# bleumaus-nrf51822-mk-1_0_1.net
KiCad netlist of a schematic drawn in EAGLE
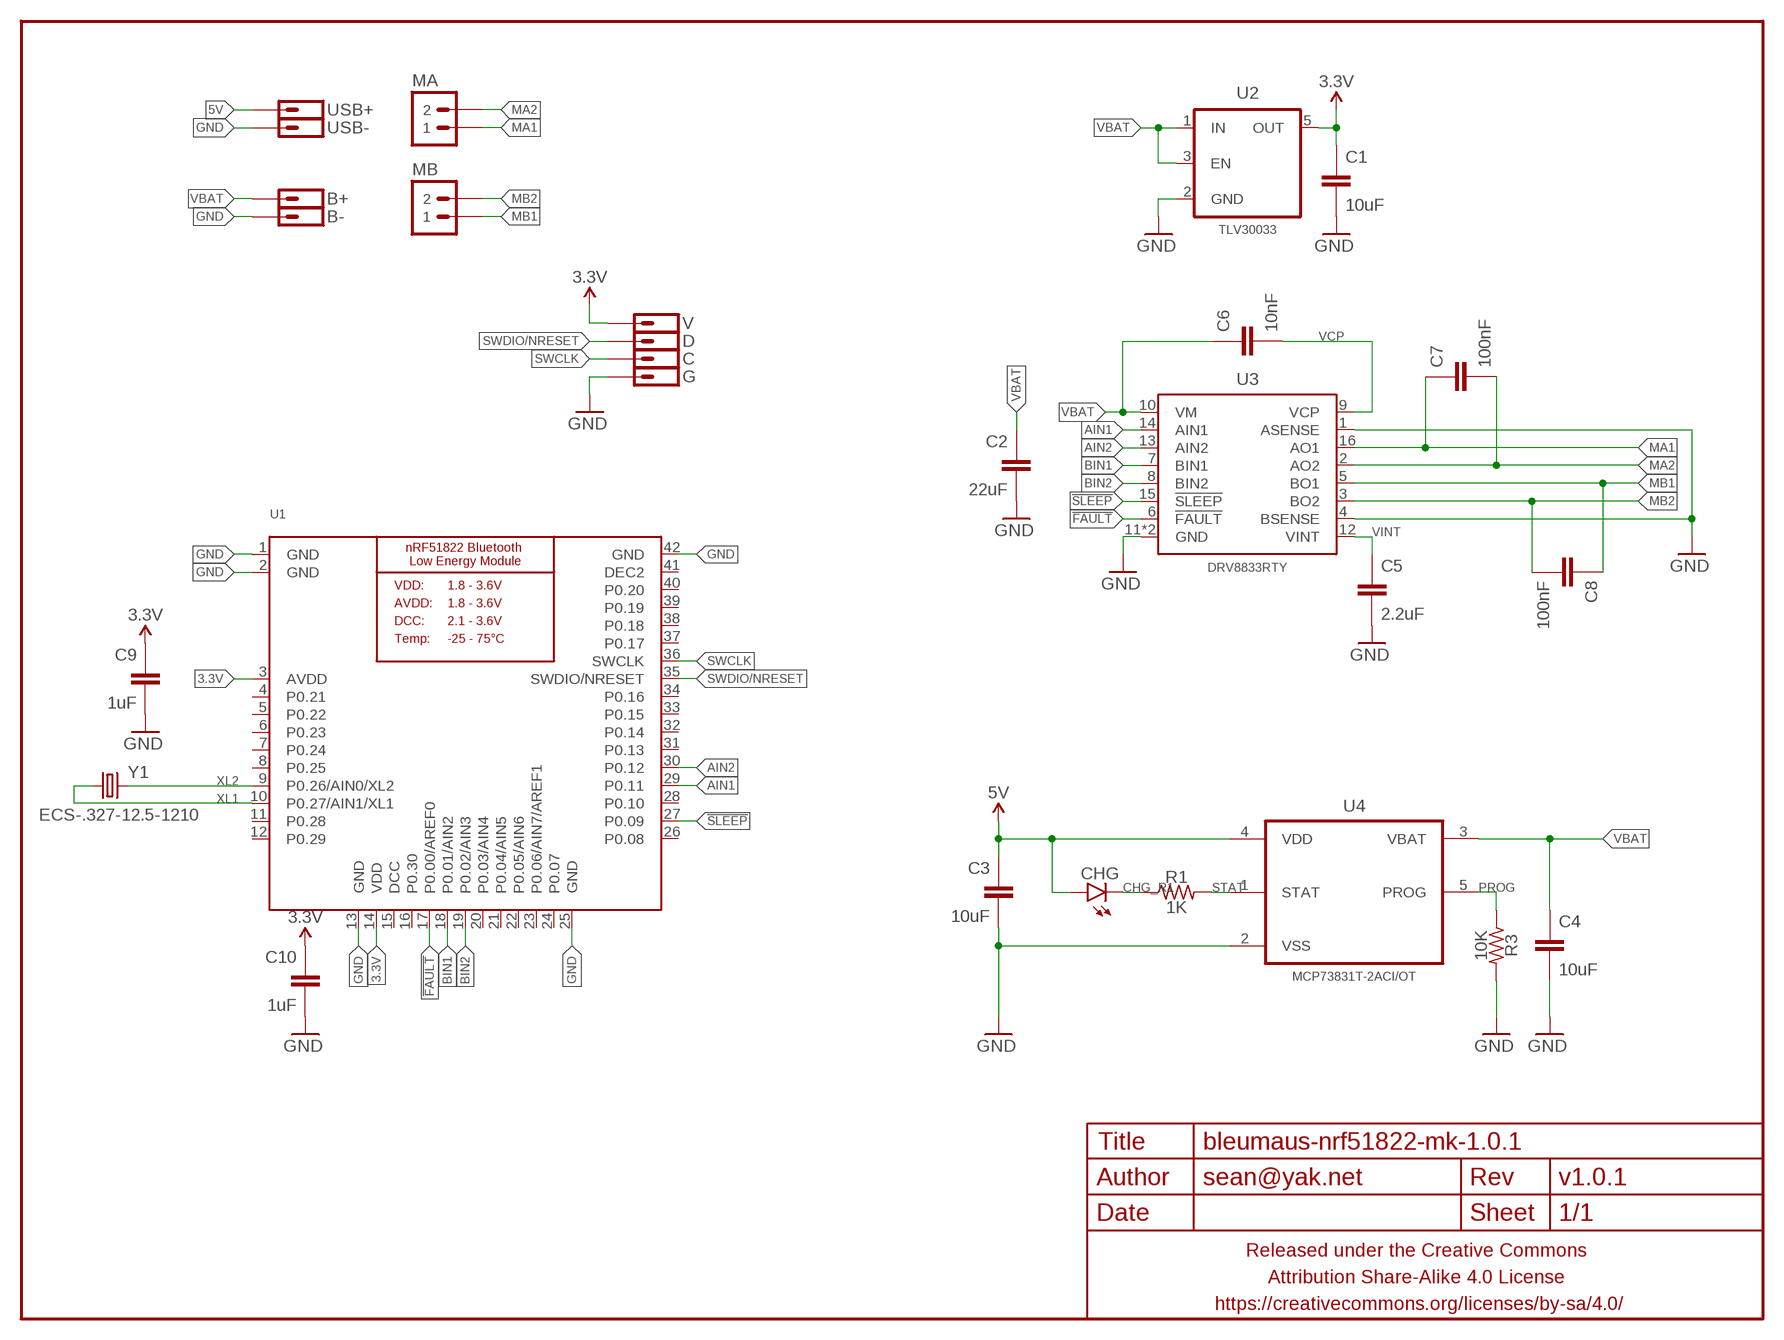
[diagram p0: schematic, sheet 1]

(export (version "E")
  (design (tool "Eeschema 10.0.6"))
  (components
    (comp (ref "B+")
      (value "M01SMD-1DIA")
      (footprint "eagle-import:1X01-SMD-1MM-DIA")
      (libsource (lib "eagle-import") (part "M01SMD-1DIA"))
    )
    (comp (ref "B-")
      (value "M01SMD-1DIA")
      (footprint "eagle-import:1X01-SMD-1MM-DIA")
      (libsource (lib "eagle-import") (part "M01SMD-1DIA"))
    )
    (comp (ref "C")
      (value "M01SMD-1DIA")
      (footprint "eagle-import:1X01-SMD-1MM-DIA")
      (libsource (lib "eagle-import") (part "M01SMD-1DIA"))
    )
    (comp (ref "C1")
      (value "10uF")
      (footprint "eagle-import:C0402")
      (libsource (lib "eagle-import") (part "CAPACITOR-CERAMICC0402"))
    )
    (comp (ref "C2")
      (value "22uF")
      (footprint "eagle-import:C1206")
      (libsource (lib "eagle-import") (part "CAPACITOR-CERAMICC1206"))
    )
    (comp (ref "C3")
      (value "10uF")
      (footprint "eagle-import:C0402")
      (libsource (lib "eagle-import") (part "CAPACITOR-CERAMICC0402"))
    )
    (comp (ref "C4")
      (value "10uF")
      (footprint "eagle-import:C0402")
      (libsource (lib "eagle-import") (part "CAPACITOR-CERAMICC0402"))
    )
    (comp (ref "C5")
      (value "2.2uF")
      (footprint "eagle-import:C0402")
      (libsource (lib "eagle-import") (part "CAPACITOR-CERAMICC0402"))
    )
    (comp (ref "C6")
      (value "10nF")
      (footprint "eagle-import:C0402")
      (libsource (lib "eagle-import") (part "CAPACITOR-CERAMICC0402"))
    )
    (comp (ref "C7")
      (value "100nF")
      (footprint "eagle-import:C0402")
      (libsource (lib "eagle-import") (part "CAPACITOR-CERAMICC0402"))
    )
    (comp (ref "C8")
      (value "100nF")
      (footprint "eagle-import:C0402")
      (libsource (lib "eagle-import") (part "CAPACITOR-CERAMICC0402"))
    )
    (comp (ref "C9")
      (value "1uF")
      (footprint "eagle-import:C0402")
      (libsource (lib "eagle-import") (part "CAPACITOR-CERAMICC0402"))
    )
    (comp (ref "C10")
      (value "1uF")
      (footprint "eagle-import:C0402")
      (libsource (lib "eagle-import") (part "CAPACITOR-CERAMICC0402"))
    )
    (comp (ref "CHG")
      (value "LED0603-TIGHT")
      (footprint "eagle-import:LED-0603-TIGHT")
      (libsource (lib "eagle-import") (part "LED0603-TIGHT"))
    )
    (comp (ref "D")
      (value "M01SMD-1DIA")
      (footprint "eagle-import:1X01-SMD-1MM-DIA")
      (libsource (lib "eagle-import") (part "M01SMD-1DIA"))
    )
    (comp (ref "FRAME1")
      (value "FRAME-LETTERNO_PACKAGE")
      (footprint "eagle-import:DUMMY")
      (fields
        (field (name "DESIGNER") "sean@yak.net")
        (field (name "VERSION") "v1.0.1")
        (field (name "DESIGNER_1") "sean@yak.net")
        (field (name "VERSION_1") "v1.0.1")
      )
      (libsource (lib "eagle-import") (part "FRAME-LETTERNO_PACKAGE"))
    )
    (comp (ref "G")
      (value "M01SMD-1DIA")
      (footprint "eagle-import:1X01-SMD-1MM-DIA")
      (libsource (lib "eagle-import") (part "M01SMD-1DIA"))
    )
    (comp (ref "MA")
      (value "M02PTH-2MM")
      (footprint "eagle-import:1X02-2MM-PTH")
      (libsource (lib "eagle-import") (part "M02PTH-2MM"))
    )
    (comp (ref "MB")
      (value "M02PTH-2MM")
      (footprint "eagle-import:1X02-2MM-PTH")
      (libsource (lib "eagle-import") (part "M02PTH-2MM"))
    )
    (comp (ref "R1")
      (value "1K")
      (footprint "eagle-import:R0402")
      (libsource (lib "eagle-import") (part "RESISTORR0402"))
    )
    (comp (ref "R3")
      (value "10K")
      (footprint "eagle-import:R0402")
      (libsource (lib "eagle-import") (part "RESISTORR0402"))
    )
    (comp (ref "U1")
      (value "NRF51822_MODULE_MDBT40")
      (footprint "eagle-import:BLE_MODULE_RAYTAC_MDBT40")
      (libsource (lib "eagle-import") (part "NRF51822_MODULE_MDBT40"))
    )
    (comp (ref "U2")
      (value "TLV30033")
      (footprint "eagle-import:SC70-TIGHTER")
      (libsource (lib "eagle-import") (part "V_REG_ENTLV700XXDCK-TIGHTER"))
    )
    (comp (ref "U3")
      (value "DRV8833RTY")
      (footprint "eagle-import:PWQFN-16")
      (libsource (lib "eagle-import") (part "DRV8833RTY"))
    )
    (comp (ref "U4")
      (value "MCP73831T-2ACI/OT")
      (footprint "eagle-import:SOT95P280X145-5N")
      (libsource (lib "eagle-import") (part "MCP73831T-2ACI/OT"))
    )
    (comp (ref "USB+")
      (value "M01SMD-1DIA")
      (footprint "eagle-import:1X01-SMD-1MM-DIA")
      (libsource (lib "eagle-import") (part "M01SMD-1DIA"))
    )
    (comp (ref "USB-")
      (value "M01SMD-1DIA")
      (footprint "eagle-import:1X01-SMD-1MM-DIA")
      (libsource (lib "eagle-import") (part "M01SMD-1DIA"))
    )
    (comp (ref "V")
      (value "M01SMD-1DIA")
      (footprint "eagle-import:1X01-SMD-1MM-DIA")
      (libsource (lib "eagle-import") (part "M01SMD-1DIA"))
    )
    (comp (ref "Y1")
      (value "ECS-.327-12.5-1210")
      (footprint "eagle-import:CRYSTAL-1X1.2MM")
      (libsource (lib "eagle-import") (part "CRYSTAL1X1.2MM"))
    )
  )
  (nets
    (net (code "1") (name "/CHG_R1") (class "Default")
      (node (ref "CHG") (pin "C") (pinfunction "C_C") (pintype "passive"))
      (node (ref "R1") (pin "1") (pinfunction "1_1") (pintype "passive"))
    )
    (net (code "2") (name "/DCC") (class "Default")
      (node (ref "U1") (pin "15") (pinfunction "DCC_15") (pintype "power_in"))
    )
    (net (code "3") (name "/DEC2") (class "Default")
      (node (ref "U1") (pin "41") (pinfunction "DEC2_41") (pintype "power_in"))
    )
    (net (code "4") (name "/PROG") (class "Default")
      (node (ref "R3") (pin "1") (pinfunction "1_1") (pintype "passive"))
      (node (ref "U4") (pin "5") (pinfunction "PROG_5") (pintype "input"))
    )
    (net (code "5") (name "/STAT") (class "Default")
      (node (ref "R1") (pin "2") (pinfunction "2_2") (pintype "passive"))
      (node (ref "U4") (pin "1") (pinfunction "STAT_1") (pintype "output"))
    )
    (net (code "6") (name "/VCP") (class "Default")
      (node (ref "C6") (pin "2") (pinfunction "2_2") (pintype "passive"))
      (node (ref "U3") (pin "9") (pinfunction "VCP_9") (pintype "bidirectional"))
    )
    (net (code "7") (name "/VINT") (class "Default")
      (node (ref "C5") (pin "1") (pinfunction "1_1") (pintype "passive"))
      (node (ref "U3") (pin "12") (pinfunction "VINT_12") (pintype "bidirectional"))
    )
    (net (code "8") (name "/XL1") (class "Default")
      (node (ref "U1") (pin "10") (pinfunction "P0.27/AIN1/XL1_10") (pintype "bidirectional"))
      (node (ref "Y1") (pin "1") (pinfunction "1_1") (pintype "passive"))
    )
    (net (code "9") (name "/XL2") (class "Default")
      (node (ref "U1") (pin "9") (pinfunction "P0.26/AIN0/XL2_9") (pintype "bidirectional"))
      (node (ref "Y1") (pin "2") (pinfunction "2_2") (pintype "passive"))
    )
    (net (code "10") (name "/~{FAULT}") (class "Default")
      (node (ref "U1") (pin "17") (pinfunction "P0.00/AREF0_17") (pintype "bidirectional"))
      (node (ref "U3") (pin "6") (pinfunction "~{FAULT}_6") (pintype "output"))
    )
    (net (code "11") (name "/~{SLEEP}") (class "Default")
      (node (ref "U1") (pin "27") (pinfunction "P0.09_27") (pintype "bidirectional"))
      (node (ref "U3") (pin "15") (pinfunction "~{SLEEP}_15") (pintype "input"))
    )
    (net (code "12") (name "3.3V") (class "Default")
      (node (ref "C1") (pin "1") (pinfunction "1_1") (pintype "passive"))
      (node (ref "C10") (pin "1") (pinfunction "1_1") (pintype "passive"))
      (node (ref "C9") (pin "1") (pinfunction "1_1") (pintype "passive"))
      (node (ref "U1") (pin "14") (pinfunction "VDD_14") (pintype "power_in"))
      (node (ref "U1") (pin "3") (pinfunction "AVDD_3") (pintype "power_in"))
      (node (ref "U2") (pin "5") (pinfunction "OUT_5") (pintype "passive"))
      (node (ref "V") (pin "P$1") (pinfunction "1_P$1") (pintype "passive"))
    )
    (net (code "13") (name "5V") (class "Default")
      (node (ref "C3") (pin "1") (pinfunction "1_1") (pintype "passive"))
      (node (ref "CHG") (pin "A") (pinfunction "A_A") (pintype "passive"))
      (node (ref "U4") (pin "4") (pinfunction "VDD_4") (pintype "power_in"))
      (node (ref "USB+") (pin "P$1") (pinfunction "1_P$1") (pintype "passive"))
    )
    (net (code "14") (name "AIN1") (class "Default")
      (node (ref "U1") (pin "29") (pinfunction "P0.11_29") (pintype "bidirectional"))
      (node (ref "U3") (pin "14") (pinfunction "AIN1_14") (pintype "input"))
    )
    (net (code "15") (name "AIN2") (class "Default")
      (node (ref "U1") (pin "30") (pinfunction "P0.12_30") (pintype "bidirectional"))
      (node (ref "U3") (pin "13") (pinfunction "AIN2_13") (pintype "input"))
    )
    (net (code "16") (name "BIN1") (class "Default")
      (node (ref "U1") (pin "18") (pinfunction "P0.01/AIN2_18") (pintype "bidirectional"))
      (node (ref "U3") (pin "7") (pinfunction "BIN1_7") (pintype "input"))
    )
    (net (code "17") (name "BIN2") (class "Default")
      (node (ref "U1") (pin "19") (pinfunction "P0.02/AIN3_19") (pintype "bidirectional"))
      (node (ref "U3") (pin "8") (pinfunction "BIN2_8") (pintype "input"))
    )
    (net (code "18") (name "GND") (class "Default")
      (node (ref "B-") (pin "P$1") (pinfunction "1_P$1") (pintype "passive"))
      (node (ref "C1") (pin "2") (pinfunction "2_2") (pintype "passive"))
      (node (ref "C10") (pin "2") (pinfunction "2_2") (pintype "passive"))
      (node (ref "C2") (pin "2") (pinfunction "2_2") (pintype "passive"))
      (node (ref "C3") (pin "2") (pinfunction "2_2") (pintype "passive"))
      (node (ref "C4") (pin "2") (pinfunction "2_2") (pintype "passive"))
      (node (ref "C5") (pin "2") (pinfunction "2_2") (pintype "passive"))
      (node (ref "C9") (pin "2") (pinfunction "2_2") (pintype "passive"))
      (node (ref "G") (pin "P$1") (pinfunction "1_P$1") (pintype "passive"))
      (node (ref "R3") (pin "2") (pinfunction "2_2") (pintype "passive"))
      (node (ref "U1") (pin "1") (pinfunction "GND_1") (pintype "power_in"))
      (node (ref "U1") (pin "13") (pinfunction "GND_13") (pintype "power_in"))
      (node (ref "U1") (pin "2") (pinfunction "GND_2") (pintype "power_in"))
      (node (ref "U1") (pin "25") (pinfunction "GND_25") (pintype "power_in"))
      (node (ref "U1") (pin "42") (pinfunction "GND_42") (pintype "power_in"))
      (node (ref "U2") (pin "2") (pinfunction "GND_2") (pintype "input"))
      (node (ref "U3") (pin "1") (pinfunction "ASENSE_1") (pintype "bidirectional"))
      (node (ref "U3") (pin "11") (pinfunction "GND_11") (pintype "bidirectional"))
      (node (ref "U3") (pin "17") (pinfunction "GND_17") (pintype "bidirectional"))
      (node (ref "U3") (pin "4") (pinfunction "BSENSE_4") (pintype "bidirectional"))
      (node (ref "U4") (pin "2") (pinfunction "VSS_2") (pintype "power_in"))
      (node (ref "USB-") (pin "P$1") (pinfunction "1_P$1") (pintype "passive"))
    )
    (net (code "19") (name "MA1") (class "Default")
      (node (ref "C7") (pin "1") (pinfunction "1_1") (pintype "passive"))
      (node (ref "MA") (pin "P$1") (pinfunction "1_P$1") (pintype "passive"))
      (node (ref "U3") (pin "16") (pinfunction "AO1_16") (pintype "bidirectional"))
    )
    (net (code "20") (name "MA2") (class "Default")
      (node (ref "C7") (pin "2") (pinfunction "2_2") (pintype "passive"))
      (node (ref "MA") (pin "P$2") (pinfunction "2_P$2") (pintype "passive"))
      (node (ref "U3") (pin "2") (pinfunction "AO2_2") (pintype "bidirectional"))
    )
    (net (code "21") (name "MB1") (class "Default")
      (node (ref "C8") (pin "1") (pinfunction "1_1") (pintype "passive"))
      (node (ref "MB") (pin "P$1") (pinfunction "1_P$1") (pintype "passive"))
      (node (ref "U3") (pin "5") (pinfunction "BO1_5") (pintype "bidirectional"))
    )
    (net (code "22") (name "MB2") (class "Default")
      (node (ref "C8") (pin "2") (pinfunction "2_2") (pintype "passive"))
      (node (ref "MB") (pin "P$2") (pinfunction "2_P$2") (pintype "passive"))
      (node (ref "U3") (pin "3") (pinfunction "BO2_3") (pintype "bidirectional"))
    )
    (net (code "23") (name "SWCLK") (class "Default")
      (node (ref "C") (pin "P$1") (pinfunction "1_P$1") (pintype "passive"))
      (node (ref "U1") (pin "36") (pinfunction "SWCLK_36") (pintype "bidirectional"))
    )
    (net (code "24") (name "SWDIO{slash}NRESET") (class "Default")
      (node (ref "D") (pin "P$1") (pinfunction "1_P$1") (pintype "passive"))
      (node (ref "U1") (pin "35") (pinfunction "SWDIO/NRESET_35") (pintype "bidirectional"))
    )
    (net (code "25") (name "VBAT") (class "Default")
      (node (ref "B+") (pin "P$1") (pinfunction "1_P$1") (pintype "passive"))
      (node (ref "C2") (pin "1") (pinfunction "1_1") (pintype "passive"))
      (node (ref "C4") (pin "1") (pinfunction "1_1") (pintype "passive"))
      (node (ref "C6") (pin "1") (pinfunction "1_1") (pintype "passive"))
      (node (ref "U2") (pin "1") (pinfunction "IN_1") (pintype "input"))
      (node (ref "U2") (pin "3") (pinfunction "EN_3") (pintype "input"))
      (node (ref "U3") (pin "10") (pinfunction "VM_10") (pintype "bidirectional"))
      (node (ref "U4") (pin "3") (pinfunction "VBAT_3") (pintype "output"))
    )
    (net (code "26") (name "unconnected-(U1-P0.03{slash}AIN4-Pad20)") (class "Default")
      (node (ref "U1") (pin "20") (pinfunction "P0.03/AIN4_20") (pintype "bidirectional"))
    )
    (net (code "27") (name "unconnected-(U1-P0.04{slash}AIN5-Pad21)") (class "Default")
      (node (ref "U1") (pin "21") (pinfunction "P0.04/AIN5_21") (pintype "bidirectional"))
    )
    (net (code "28") (name "unconnected-(U1-P0.05{slash}AIN6-Pad22)") (class "Default")
      (node (ref "U1") (pin "22") (pinfunction "P0.05/AIN6_22") (pintype "bidirectional"))
    )
    (net (code "29") (name "unconnected-(U1-P0.06{slash}AIN7{slash}AREF1-Pad23)") (class "Default")
      (node (ref "U1") (pin "23") (pinfunction "P0.06/AIN7/AREF1_23") (pintype "bidirectional"))
    )
    (net (code "30") (name "unconnected-(U1-P0.07-Pad24)") (class "Default")
      (node (ref "U1") (pin "24") (pinfunction "P0.07_24") (pintype "bidirectional"))
    )
    (net (code "31") (name "unconnected-(U1-P0.08-Pad26)") (class "Default")
      (node (ref "U1") (pin "26") (pinfunction "P0.08_26") (pintype "bidirectional"))
    )
    (net (code "32") (name "unconnected-(U1-P0.10-Pad28)") (class "Default")
      (node (ref "U1") (pin "28") (pinfunction "P0.10_28") (pintype "bidirectional"))
    )
    (net (code "33") (name "unconnected-(U1-P0.13-Pad31)") (class "Default")
      (node (ref "U1") (pin "31") (pinfunction "P0.13_31") (pintype "bidirectional"))
    )
    (net (code "34") (name "unconnected-(U1-P0.14-Pad32)") (class "Default")
      (node (ref "U1") (pin "32") (pinfunction "P0.14_32") (pintype "bidirectional"))
    )
    (net (code "35") (name "unconnected-(U1-P0.15-Pad33)") (class "Default")
      (node (ref "U1") (pin "33") (pinfunction "P0.15_33") (pintype "bidirectional"))
    )
    (net (code "36") (name "unconnected-(U1-P0.16-Pad34)") (class "Default")
      (node (ref "U1") (pin "34") (pinfunction "P0.16_34") (pintype "bidirectional"))
    )
    (net (code "37") (name "unconnected-(U1-P0.17-Pad37)") (class "Default")
      (node (ref "U1") (pin "37") (pinfunction "P0.17_37") (pintype "bidirectional"))
    )
    (net (code "38") (name "unconnected-(U1-P0.18-Pad38)") (class "Default")
      (node (ref "U1") (pin "38") (pinfunction "P0.18_38") (pintype "bidirectional"))
    )
    (net (code "39") (name "unconnected-(U1-P0.19-Pad39)") (class "Default")
      (node (ref "U1") (pin "39") (pinfunction "P0.19_39") (pintype "bidirectional"))
    )
    (net (code "40") (name "unconnected-(U1-P0.20-Pad40)") (class "Default")
      (node (ref "U1") (pin "40") (pinfunction "P0.20_40") (pintype "bidirectional"))
    )
    (net (code "41") (name "unconnected-(U1-P0.21-Pad4)") (class "Default")
      (node (ref "U1") (pin "4") (pinfunction "P0.21_4") (pintype "bidirectional"))
    )
    (net (code "42") (name "unconnected-(U1-P0.22-Pad5)") (class "Default")
      (node (ref "U1") (pin "5") (pinfunction "P0.22_5") (pintype "bidirectional"))
    )
    (net (code "43") (name "unconnected-(U1-P0.23-Pad6)") (class "Default")
      (node (ref "U1") (pin "6") (pinfunction "P0.23_6") (pintype "bidirectional"))
    )
    (net (code "44") (name "unconnected-(U1-P0.24-Pad7)") (class "Default")
      (node (ref "U1") (pin "7") (pinfunction "P0.24_7") (pintype "bidirectional"))
    )
    (net (code "45") (name "unconnected-(U1-P0.25-Pad8)") (class "Default")
      (node (ref "U1") (pin "8") (pinfunction "P0.25_8") (pintype "bidirectional"))
    )
    (net (code "46") (name "unconnected-(U1-P0.28-Pad11)") (class "Default")
      (node (ref "U1") (pin "11") (pinfunction "P0.28_11") (pintype "bidirectional"))
    )
    (net (code "47") (name "unconnected-(U1-P0.29-Pad12)") (class "Default")
      (node (ref "U1") (pin "12") (pinfunction "P0.29_12") (pintype "bidirectional"))
    )
    (net (code "48") (name "unconnected-(U1-P0.30-Pad16)") (class "Default")
      (node (ref "U1") (pin "16") (pinfunction "P0.30_16") (pintype "bidirectional"))
    )
  )
)
